# SoftCore_SA_P7.net
KiCad netlist of a schematic drawn in Altium Designer
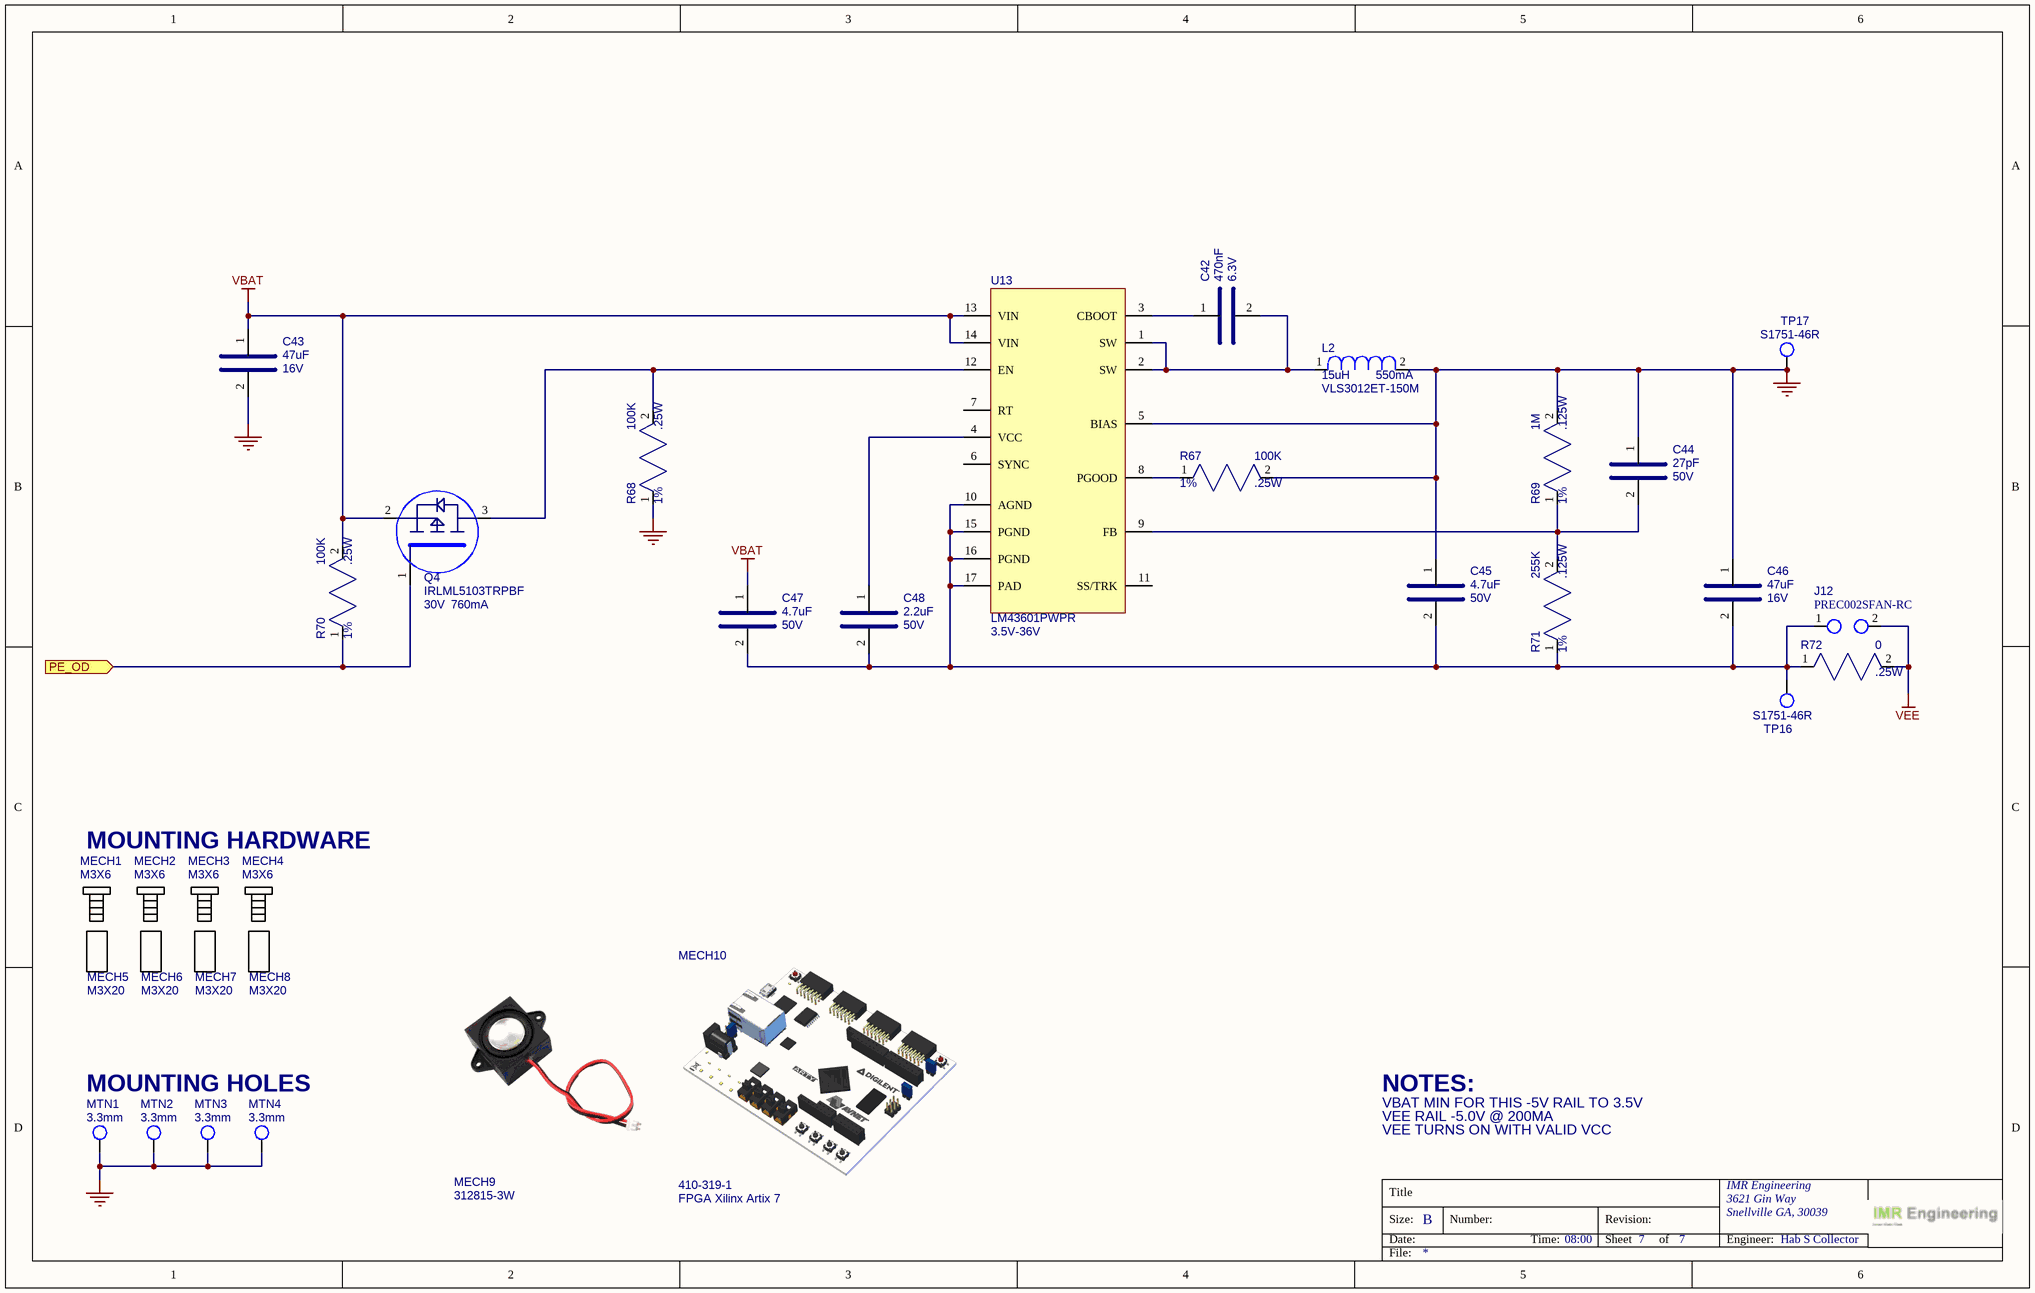
[diagram p0: SoftCore_SA_P7.SchDoc]

(export (version "E")
  (design (tool "Eeschema 10.0.6"))
  (components
    (comp (ref "C42")
      (value "470nF")
      (footprint "CAP_0805")
      (description "CAP CER 0.47UF 6.3V X5R 0402")
      (fields
        (field (name "MFG") "Murata Electronics")
        (field (name "VOLTAGE") "6.3V")
        (field (name "Comment") "GRM155R60J474KE19D")
      )
      (libsource (lib "IMR_LIB_SCH_R2") (part "CAP_SMD_470NF_50V_0805"))
    )
    (comp (ref "C43")
      (value "47uF")
      (footprint "CAP_1210")
      (description "CAP CER 47UF 50V X5R 1210")
      (fields
        (field (name "MFG") "Murata Electronics")
        (field (name "VOLTAGE") "16V")
        (field (name "Comment") "GRM32ER60J476ME20L")
      )
      (libsource (lib "IMR_LIB_SCH_R2") (part "CAP_SMD_47UF_16V_1210"))
    )
    (comp (ref "C44")
      (value "27pF")
      (footprint "CAP_0805")
      (description "CAP CER 27PF 50V C0G/NP0 0805")
      (fields
        (field (name "MFG") "KEMET")
        (field (name "VOLTAGE") "50V")
        (field (name "Comment") "C0805C270J5GACTU")
      )
      (libsource (lib "IMR_LIB_SCH_R2") (part "CAP_SMD_27PF_50V_0805"))
    )
    (comp (ref "C45")
      (value "4.7uF")
      (footprint "CAP_0805")
      (description "CAP CER 4.7UF 50V X5R 0805")
      (fields
        (field (name "MFG") "Murata Electronics")
        (field (name "VOLTAGE") "50V")
        (field (name "Comment") "GRM21BR61H475KE51L")
      )
      (libsource (lib "IMR_LIB_SCH_R2") (part "CAP_SMD_4.7UF_50V_0805"))
    )
    (comp (ref "C46")
      (value "47uF")
      (footprint "CAP_1210")
      (description "CAP CER 47UF 50V X5R 1210")
      (fields
        (field (name "MFG") "Murata Electronics")
        (field (name "VOLTAGE") "16V")
        (field (name "Comment") "GRM32ER60J476ME20L")
      )
      (libsource (lib "IMR_LIB_SCH_R2") (part "CAP_SMD_47UF_16V_1210"))
    )
    (comp (ref "C47")
      (value "4.7uF")
      (footprint "CAP_0805")
      (description "CAP CER 4.7UF 50V X5R 0805")
      (fields
        (field (name "MFG") "Murata Electronics")
        (field (name "VOLTAGE") "50V")
        (field (name "Comment") "GRM21BR61H475KE51L")
      )
      (libsource (lib "IMR_LIB_SCH_R2") (part "CAP_SMD_4.7UF_50V_0805"))
    )
    (comp (ref "C48")
      (value "2.2uF")
      (footprint "CAP_0805")
      (description "CAP CER 2.2UF 50V X5R 0805")
      (fields
        (field (name "MFG") "Murata Electronics")
        (field (name "VOLTAGE") "50V")
        (field (name "Comment") "GRM219R61E225KA12J")
      )
      (libsource (lib "IMR_LIB_SCH_R2") (part "CAP_SMD_2.2UF_50V_0805"))
    )
    (comp (ref "J12")
      (value "PREC002SFAN-RC")
      (footprint "HDR_1X2_100MILL")
      (description "CONN HEADER VERT 2POS 2.54MM")
      (fields (field (name "MFG") "Sullins Connector Solutions"))
      (libsource (lib "IMR_LIB_SCH_R2") (part "CONN_JUMPER_2P_100MIL_VERT"))
    )
    (comp (ref "L2")
      (value "15uH")
      (footprint "IND_VLS3012ET-150M")
      (description "FIXED IND 15UH 550MA 516MOHM SMD")
      (fields
        (field (name "MFG") "TDK Corporation")
        (field (name "TOLERANCE") "20%")
        (field (name "MFG_PN") "VLS3012ET-150M")
        (field (name "CURRENT") "550mA")
      )
      (libsource (lib "IMR_LIB_SCH_R2") (part "INDUCTOR_VLS3012ET-150M"))
    )
    (comp (ref "MECH1")
      (value "RM3X6MM 2701")
      (footprint "MECHANICAL_SCREW_M3X6")
      (description "SCREW M3X6 PAN HEAD SS")
      (fields (field (name "MFG") "APM Hexseal") (field (name "SIZE") "M3X6"))
      (libsource (lib "IMR_LIB_SCH_R2") (part "MECHANICAL_SCREW_M3X6_PAN_HEAD"))
    )
    (comp (ref "MECH2")
      (value "RM3X6MM 2701")
      (footprint "MECHANICAL_SCREW_M3X6")
      (description "SCREW M3X6 PAN HEAD SS")
      (fields (field (name "MFG") "APM Hexseal") (field (name "SIZE") "M3X6"))
      (libsource (lib "IMR_LIB_SCH_R2") (part "MECHANICAL_SCREW_M3X6_PAN_HEAD"))
    )
    (comp (ref "MECH3")
      (value "RM3X6MM 2701")
      (footprint "MECHANICAL_SCREW_M3X6")
      (description "SCREW M3X6 PAN HEAD SS")
      (fields (field (name "MFG") "APM Hexseal") (field (name "SIZE") "M3X6"))
      (libsource (lib "IMR_LIB_SCH_R2") (part "MECHANICAL_SCREW_M3X6_PAN_HEAD"))
    )
    (comp (ref "MECH4")
      (value "RM3X6MM 2701")
      (footprint "MECHANICAL_SCREW_M3X6")
      (description "SCREW M3X6 PAN HEAD SS")
      (fields (field (name "MFG") "APM Hexseal") (field (name "SIZE") "M3X6"))
      (libsource (lib "IMR_LIB_SCH_R2") (part "MECHANICAL_SCREW_M3X6_PAN_HEAD"))
    )
    (comp (ref "MECH5")
      (value "24407")
      (footprint "MECHANICAL_SPACER_F_F_M3X20")
      (description "HEX STANDOFF M3 BRASS 20MM")
      (fields (field (name "MFG") "Keystone Electronics") (field (name "SIZE") "M3X20"))
      (libsource (lib "IMR_LIB_SCH_R2") (part "MECHANICAL_STANDOFF_M3X20"))
    )
    (comp (ref "MECH6")
      (value "24407")
      (footprint "MECHANICAL_SPACER_F_F_M3X20")
      (description "HEX STANDOFF M3 BRASS 20MM")
      (fields (field (name "MFG") "Keystone Electronics") (field (name "SIZE") "M3X20"))
      (libsource (lib "IMR_LIB_SCH_R2") (part "MECHANICAL_STANDOFF_M3X20"))
    )
    (comp (ref "MECH7")
      (value "24407")
      (footprint "MECHANICAL_SPACER_F_F_M3X20")
      (description "HEX STANDOFF M3 BRASS 20MM")
      (fields (field (name "MFG") "Keystone Electronics") (field (name "SIZE") "M3X20"))
      (libsource (lib "IMR_LIB_SCH_R2") (part "MECHANICAL_STANDOFF_M3X20"))
    )
    (comp (ref "MECH8")
      (value "24407")
      (footprint "MECHANICAL_SPACER_F_F_M3X20")
      (description "HEX STANDOFF M3 BRASS 20MM")
      (fields (field (name "MFG") "Keystone Electronics") (field (name "SIZE") "M3X20"))
      (libsource (lib "IMR_LIB_SCH_R2") (part "MECHANICAL_STANDOFF_M3X20"))
    )
    (comp (ref "MECH9")
      (value "312815-3W")
      (footprint "312815-3W_PCB")
      (description "SPEAKER PANEL MOUNT")
      (fields (field (name "MFG") "ARDUINO") (field (name "MFG_PN") "312815-3W"))
      (libsource (lib "IMR_LIB_SCH_R2") (part "MECHANICAL_SPEAKER_MOUNTED"))
    )
    (comp (ref "MECH10")
      (value "FPGA Xilinx Artix 7")
      (footprint "ARTY_A7_DEV_BOARD")
      (description "DEVELOPMENT BOARD FPGA XILINX A7")
      (fields
        (field (name "MFG") "Digilent, Inc.")
        (field (name "MFG_PN") "410-319-1")
        (field (name "Comment") "410-319-1")
      )
      (libsource (lib "IMR_LIB_SCH_R2") (part "MODULE_ARTY_A7"))
    )
    (comp (ref "MTN1")
      (value "~")
      (footprint "PMG_MT_HOLE_3.3MM")
      (description "MOUNTING HOLE 3.3MM")
      (fields (field (name "HOLE SIZE") "3.3mm"))
      (libsource (lib "IMR_LIB_SCH_R2") (part "MTN_HOLE_3.3MM"))
    )
    (comp (ref "MTN2")
      (value "~")
      (footprint "PMG_MT_HOLE_3.3MM")
      (description "MOUNTING HOLE 3.3MM")
      (fields (field (name "HOLE SIZE") "3.3mm"))
      (libsource (lib "IMR_LIB_SCH_R2") (part "MTN_HOLE_3.3MM"))
    )
    (comp (ref "MTN3")
      (value "~")
      (footprint "PMG_MT_HOLE_3.3MM")
      (description "MOUNTING HOLE 3.3MM")
      (fields (field (name "HOLE SIZE") "3.3mm"))
      (libsource (lib "IMR_LIB_SCH_R2") (part "MTN_HOLE_3.3MM"))
    )
    (comp (ref "MTN4")
      (value "~")
      (footprint "PMG_MT_HOLE_3.3MM")
      (description "MOUNTING HOLE 3.3MM")
      (fields (field (name "HOLE SIZE") "3.3mm"))
      (libsource (lib "IMR_LIB_SCH_R2") (part "MTN_HOLE_3.3MM"))
    )
    (comp (ref "Q4")
      (value "30V")
      (footprint "SOT-23")
      (description "MOSFET P-CH 30V 760MA SOT23")
      (fields
        (field (name "MFG") "Infineon Technologies")
        (field (name "MFG_PN") "IRLML5103TRPBF")
        (field (name "CURRENT") "760mA")
        (field (name "Comment") "IRLML5103TRPBF")
      )
      (libsource (lib "IMR_LIB_SCH_R2") (part "MOSFET_PCH_IRLML5103TRPBF"))
    )
    (comp (ref "R67")
      (value "100K")
      (footprint "RES_0805")
      (description "RES SMD 100K OHM 1% 1/4W 0805")
      (fields
        (field (name "MFG") "Yageo")
        (field (name "POWER") ".25W")
        (field (name "TOLERANCE") "1%")
        (field (name "Comment") "RC0805FR-07100KL")
      )
      (libsource (lib "IMR_LIB_SCH_R2") (part "RES_SMD_100K_0805_1/4W_1%"))
    )
    (comp (ref "R68")
      (value "100K")
      (footprint "RES_0805")
      (description "RES SMD 100K OHM 1% 1/4W 0805")
      (fields
        (field (name "MFG") "Yageo")
        (field (name "POWER") ".25W")
        (field (name "TOLERANCE") "1%")
        (field (name "Comment") "RC0805FR-07100KL")
      )
      (libsource (lib "IMR_LIB_SCH_R2") (part "RES_SMD_100K_0805_1/4W_1%"))
    )
    (comp (ref "R69")
      (value "1M")
      (footprint "RES_0805")
      (description "RES SMD 1M OHM 1% 1/8W 0805")
      (fields
        (field (name "MFG") "Yageo")
        (field (name "POWER") ".125W")
        (field (name "TOLERANCE") "1%")
        (field (name "Comment") "RC0805FR-071ML")
      )
      (libsource (lib "IMR_LIB_SCH_R2") (part "RES_SMD_1M_0805_1/8W_1%"))
    )
    (comp (ref "R70")
      (value "100K")
      (footprint "RES_0805")
      (description "RES SMD 100K OHM 1% 1/4W 0805")
      (fields
        (field (name "MFG") "Yageo")
        (field (name "POWER") ".25W")
        (field (name "TOLERANCE") "1%")
        (field (name "Comment") "RC0805FR-07100KL")
      )
      (libsource (lib "IMR_LIB_SCH_R2") (part "RES_SMD_100K_0805_1/4W_1%"))
    )
    (comp (ref "R71")
      (value "255K")
      (footprint "RES_0805")
      (description "RES SMD 255K OHM 1% 1/8W 0805")
      (fields
        (field (name "MFG") "Yageo")
        (field (name "POWER") ".125W")
        (field (name "TOLERANCE") "1%")
        (field (name "Comment") "RC0805FR-07255KL")
      )
      (libsource (lib "IMR_LIB_SCH_R2") (part "RES_SMD_255K_0805_1/8W_1%"))
    )
    (comp (ref "R72")
      (value "0")
      (footprint "RES_0805")
      (description "RES SMD 0 OHM 1% 1/8W 0805")
      (fields (field (name "MFG") "Yageo") (field (name "TOLERANCE") "1%") (field (name "POWER") ".25W"))
      (libsource (lib "IMR_LIB_SCH_R2") (part "RES_SMD_0_0805_1/8W_1%"))
    )
    (comp (ref "TP16")
      (value "S1751-46R")
      (footprint "HARWIN_S1751")
      (description "PCB TEST POINT CONNECT")
      (fields (field (name "MFG") "Harwin Inc") (field (name "MFG_PN") "S1751-46R"))
      (libsource (lib "IMR_LIB_SCH_R2") (part "CONN_TEST_POINT_S1751-46R"))
    )
    (comp (ref "TP17")
      (value "S1751-46R")
      (footprint "HARWIN_S1751")
      (description "PCB TEST POINT CONNECT")
      (fields (field (name "MFG") "Harwin Inc") (field (name "MFG_PN") "S1751-46R"))
      (libsource (lib "IMR_LIB_SCH_R2") (part "CONN_TEST_POINT_S1751-46R"))
    )
    (comp (ref "U13")
      (value "3.5V-36V")
      (footprint "SOP65P640X120-17N")
      (description "IC REG BUCK ADJ 1A 16HTSSOP")
      (fields
        (field (name "MFG") "Texas Instruments")
        (field (name "MFG_PN") "LM43601PWPR")
        (field (name "Comment") "LM43601PWPR")
      )
      (libsource (lib "IMR_LIB_SCH_R2") (part "IC_SMPS_LM43601PWPR"))
    )
  )
  (nets
    (net (code "1") (name "/PE_OD") (class "Default")
      (node (ref "Q4") (pin "1") (pinfunction "G_1") (pintype "passive"))
      (node (ref "R70") (pin "1") (pinfunction "1_1") (pintype "passive"))
    )
    (net (code "2") (name "GND") (class "Default")
      (node (ref "C43") (pin "2") (pinfunction "2_2") (pintype "passive"))
      (node (ref "C44") (pin "1") (pinfunction "1_1") (pintype "passive"))
      (node (ref "C45") (pin "1") (pinfunction "1_1") (pintype "passive"))
      (node (ref "C46") (pin "1") (pinfunction "1_1") (pintype "passive"))
      (node (ref "L2") (pin "2") (pinfunction "2_2") (pintype "passive"))
      (node (ref "MTN1") (pin "1") (pintype "passive"))
      (node (ref "MTN2") (pin "1") (pintype "passive"))
      (node (ref "MTN3") (pin "1") (pintype "passive"))
      (node (ref "MTN4") (pin "1") (pintype "passive"))
      (node (ref "R67") (pin "2") (pinfunction "2_2") (pintype "passive"))
      (node (ref "R68") (pin "1") (pinfunction "1_1") (pintype "passive"))
      (node (ref "R69") (pin "2") (pinfunction "2_2") (pintype "passive"))
      (node (ref "TP17") (pin "1") (pintype "passive"))
      (node (ref "U13") (pin "5") (pinfunction "BIAS_5") (pintype "passive"))
    )
    (net (code "3") (name "Net-(C42-Pad2)") (class "Default")
      (node (ref "C42") (pin "2") (pinfunction "2_2") (pintype "passive"))
      (node (ref "L2") (pin "1") (pinfunction "1_1") (pintype "passive"))
      (node (ref "U13") (pin "1") (pinfunction "SW_1") (pintype "passive"))
      (node (ref "U13") (pin "2") (pinfunction "SW_2") (pintype "passive"))
    )
    (net (code "4") (name "Net-(Q4-D)") (class "Default")
      (node (ref "Q4") (pin "3") (pinfunction "D_3") (pintype "passive"))
      (node (ref "R68") (pin "2") (pinfunction "2_2") (pintype "passive"))
      (node (ref "U13") (pin "12") (pinfunction "EN_12") (pintype "passive"))
    )
    (net (code "5") (name "Net-(U13-AGND)") (class "Default")
      (node (ref "C45") (pin "2") (pinfunction "2_2") (pintype "passive"))
      (node (ref "C46") (pin "2") (pinfunction "2_2") (pintype "passive"))
      (node (ref "C47") (pin "2") (pinfunction "2_2") (pintype "passive"))
      (node (ref "C48") (pin "2") (pinfunction "2_2") (pintype "passive"))
      (node (ref "J12") (pin "1") (pintype "passive"))
      (node (ref "R71") (pin "1") (pinfunction "1_1") (pintype "passive"))
      (node (ref "R72") (pin "1") (pinfunction "1_1") (pintype "passive"))
      (node (ref "TP16") (pin "1") (pintype "passive"))
      (node (ref "U13") (pin "10") (pinfunction "AGND_10") (pintype "passive"))
      (node (ref "U13") (pin "15") (pinfunction "PGND_15") (pintype "passive"))
      (node (ref "U13") (pin "16") (pinfunction "PGND_16") (pintype "passive"))
      (node (ref "U13") (pin "17") (pinfunction "PAD_17") (pintype "passive"))
    )
    (net (code "6") (name "Net-(U13-CBOOT)") (class "Default")
      (node (ref "C42") (pin "1") (pinfunction "1_1") (pintype "passive"))
      (node (ref "U13") (pin "3") (pinfunction "CBOOT_3") (pintype "passive"))
    )
    (net (code "7") (name "Net-(U13-FB)") (class "Default")
      (node (ref "C44") (pin "2") (pinfunction "2_2") (pintype "passive"))
      (node (ref "R69") (pin "1") (pinfunction "1_1") (pintype "passive"))
      (node (ref "R71") (pin "2") (pinfunction "2_2") (pintype "passive"))
      (node (ref "U13") (pin "9") (pinfunction "FB_9") (pintype "passive"))
    )
    (net (code "8") (name "Net-(U13-PGOOD)") (class "Default")
      (node (ref "R67") (pin "1") (pinfunction "1_1") (pintype "passive"))
      (node (ref "U13") (pin "8") (pinfunction "PGOOD_8") (pintype "passive"))
    )
    (net (code "9") (name "Net-(U13-VCC)") (class "Default")
      (node (ref "C48") (pin "1") (pinfunction "1_1") (pintype "passive"))
      (node (ref "U13") (pin "4") (pinfunction "VCC_4") (pintype "passive"))
    )
    (net (code "10") (name "VBAT") (class "Default")
      (node (ref "C43") (pin "1") (pinfunction "1_1") (pintype "passive"))
      (node (ref "C47") (pin "1") (pinfunction "1_1") (pintype "passive"))
      (node (ref "Q4") (pin "2") (pinfunction "S_2") (pintype "passive"))
      (node (ref "R70") (pin "2") (pinfunction "2_2") (pintype "passive"))
      (node (ref "U13") (pin "13") (pinfunction "VIN_13") (pintype "passive"))
      (node (ref "U13") (pin "14") (pinfunction "VIN_14") (pintype "passive"))
    )
    (net (code "11") (name "VEE") (class "Default")
      (node (ref "J12") (pin "2") (pintype "passive"))
      (node (ref "R72") (pin "2") (pinfunction "2_2") (pintype "passive"))
    )
    (net (code "12") (name "unconnected-(U13-RT-Pad7)") (class "Default")
      (node (ref "U13") (pin "7") (pinfunction "RT_7") (pintype "passive"))
    )
    (net (code "13") (name "unconnected-(U13-SS{slash}TRK-Pad11)") (class "Default")
      (node (ref "U13") (pin "11") (pinfunction "SS/TRK_11") (pintype "passive"))
    )
    (net (code "14") (name "unconnected-(U13-SYNC-Pad6)") (class "Default")
      (node (ref "U13") (pin "6") (pinfunction "SYNC_6") (pintype "passive"))
    )
  )
)
